# SLD-1550-ANR.net
KiCad netlist of a schematic drawn in Altium Designer
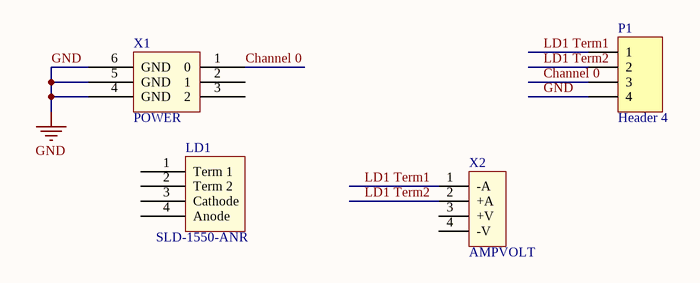
[diagram p0: SLD-1550-ANR.SchDoc]

(export (version "E")
  (design (tool "Eeschema 10.0.6"))
  (components
    (comp (ref "LD1")
      (value "SLD-1550-ANR")
      (footprint "aab_Active:СЛД-1550-АНР")
      (libsource (lib "aab_Schlib") (part "SLD-1550-ANR"))
    )
    (comp (ref "P1")
      (value "Header 4")
      (footprint "HDR1X4")
      (description "Header, 4-Pin")
      (fields (field (name "PUBLISHER") "Altium Limited"))
      (libsource (lib "Miscellaneous Connectors") (part "Header 4"))
    )
    (comp (ref "X1") (value "POWER") (footprint "POWER") (libsource (lib "vpl_Schlib") (part "POWER")))
    (comp (ref "X2")
      (value "AMPVOLT")
      (footprint "AMP_VOLTMETER")
      (libsource (lib "vpl_Schlib") (part "AMP_VOLTMETER"))
    )
  )
  (nets
    (net (code "1") (name "/Channel 0") (class "Default")
      (node (ref "P1") (pin "3") (pinfunction "3_3") (pintype "passive"))
      (node (ref "X1") (pin "1") (pinfunction "0_1") (pintype "passive"))
    )
    (net (code "2") (name "/LD1 Term1") (class "Default")
      (node (ref "P1") (pin "1") (pinfunction "1_1") (pintype "passive"))
      (node (ref "X2") (pin "1") (pinfunction "-A_1") (pintype "passive"))
    )
    (net (code "3") (name "/LD1 Term2") (class "Default")
      (node (ref "P1") (pin "2") (pinfunction "2_2") (pintype "passive"))
      (node (ref "X2") (pin "2") (pinfunction "+A_2") (pintype "passive"))
    )
    (net (code "4") (name "GND") (class "Default")
      (node (ref "P1") (pin "4") (pinfunction "4_4") (pintype "passive"))
      (node (ref "X1") (pin "4") (pinfunction "GND_4") (pintype "passive"))
      (node (ref "X1") (pin "5") (pinfunction "GND_5") (pintype "passive"))
      (node (ref "X1") (pin "6") (pinfunction "GND_6") (pintype "passive"))
    )
    (net (code "5") (name "unconnected-(LD1-Anode-Pad4)") (class "Default")
      (node (ref "LD1") (pin "4") (pinfunction "Anode_4") (pintype "passive"))
    )
    (net (code "6") (name "unconnected-(LD1-Cathode-Pad3)") (class "Default")
      (node (ref "LD1") (pin "3") (pinfunction "Cathode_3") (pintype "passive"))
    )
    (net (code "7") (name "unconnected-(LD1-Term_1-Pad1)") (class "Default")
      (node (ref "LD1") (pin "1") (pinfunction "Term_1_1") (pintype "passive"))
    )
    (net (code "8") (name "unconnected-(LD1-Term_2-Pad2)") (class "Default")
      (node (ref "LD1") (pin "2") (pinfunction "Term_2_2") (pintype "passive"))
    )
    (net (code "9") (name "unconnected-(X1-1-Pad2)") (class "Default")
      (node (ref "X1") (pin "2") (pinfunction "1_2") (pintype "passive"))
    )
    (net (code "10") (name "unconnected-(X1-2-Pad3)") (class "Default")
      (node (ref "X1") (pin "3") (pinfunction "2_3") (pintype "passive"))
    )
    (net (code "11") (name "unconnected-(X2-+V-Pad3)") (class "Default")
      (node (ref "X2") (pin "3") (pinfunction "+V_3") (pintype "passive"))
    )
    (net (code "12") (name "unconnected-(X2--V-Pad4)") (class "Default")
      (node (ref "X2") (pin "4") (pinfunction "-V_4") (pintype "passive"))
    )
  )
)
